# TMS320VC5509AMINI.net
KiCad netlist of a schematic drawn in Altium Designer
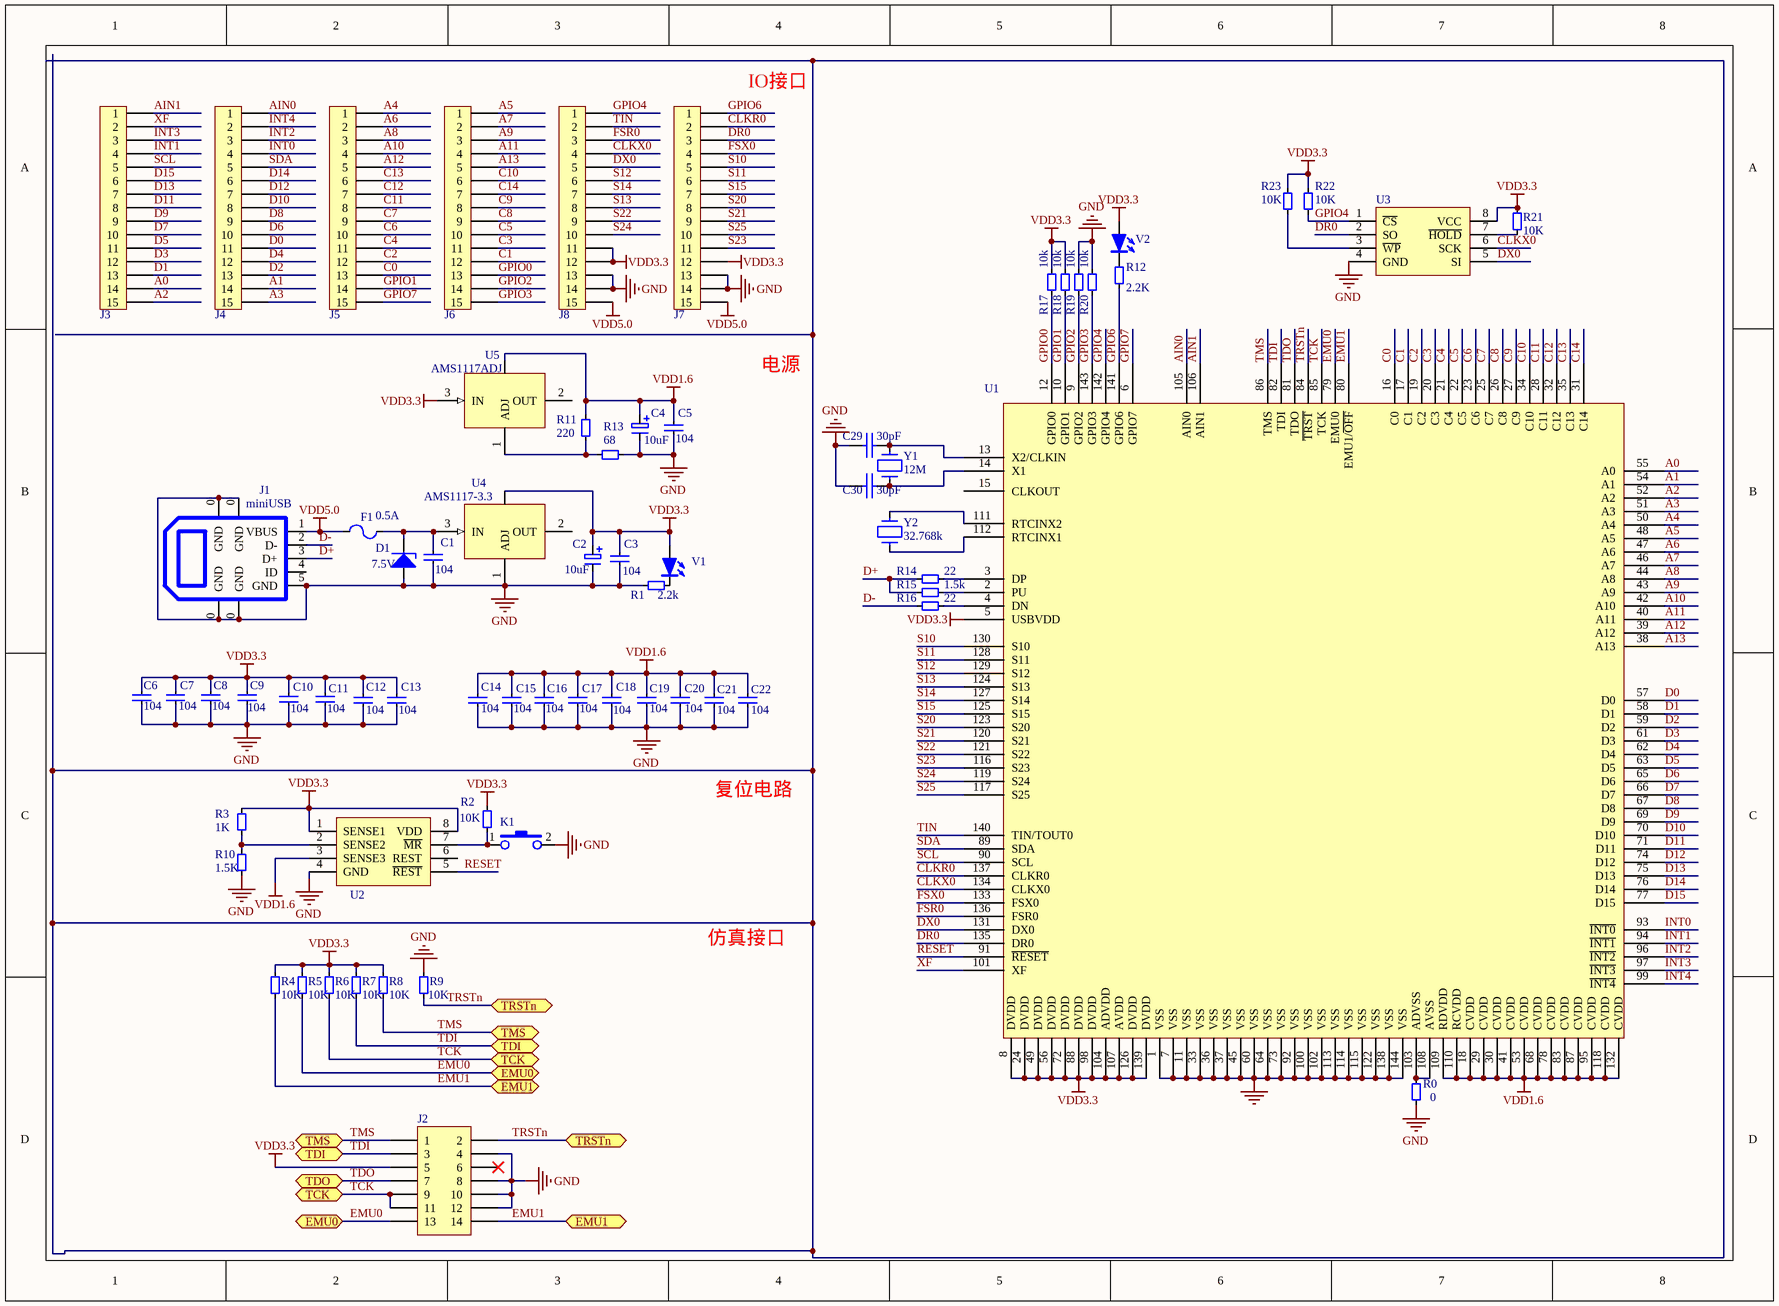
[diagram p0: TMS320VC5509AMINI.SchDoc]

(export (version "E")
  (design (tool "Eeschema 10.0.6"))
  (components
    (comp (ref "C1") (value "104") (footprint "0805_C_M") (libsource (lib "电容系列") (part "C3")))
    (comp (ref "C2") (value "10uF") (footprint "CAP-B") (libsource (lib "电容系列") (part "E3")))
    (comp (ref "C3") (value "104") (footprint "0805_C_M") (libsource (lib "电容系列") (part "C3")))
    (comp (ref "C4") (value "10uF") (footprint "CAP-B") (libsource (lib "电容系列") (part "E3")))
    (comp (ref "C5") (value "104") (footprint "0805_C_M") (libsource (lib "电容系列") (part "C3")))
    (comp (ref "C6") (value "104") (footprint "0805_C_M") (libsource (lib "电容系列") (part "C3")))
    (comp (ref "C7") (value "104") (footprint "0805_C_M") (libsource (lib "电容系列") (part "C3")))
    (comp (ref "C8") (value "104") (footprint "0805_C_M") (libsource (lib "电容系列") (part "C3")))
    (comp (ref "C9") (value "104") (footprint "0805_C_M") (libsource (lib "电容系列") (part "C3")))
    (comp (ref "C10") (value "104") (footprint "0805_C_M") (libsource (lib "电容系列") (part "C3")))
    (comp (ref "C11") (value "104") (footprint "0805_C_M") (libsource (lib "电容系列") (part "C3")))
    (comp (ref "C12") (value "104") (footprint "0805_C_M") (libsource (lib "电容系列") (part "C3")))
    (comp (ref "C13") (value "104") (footprint "0805_C_M") (libsource (lib "电容系列") (part "C3")))
    (comp (ref "C14") (value "104") (footprint "0805_C_M") (libsource (lib "电容系列") (part "C3")))
    (comp (ref "C15") (value "104") (footprint "0805_C_M") (libsource (lib "电容系列") (part "C3")))
    (comp (ref "C16") (value "104") (footprint "0805_C_M") (libsource (lib "电容系列") (part "C3")))
    (comp (ref "C17") (value "104") (footprint "0805_C_M") (libsource (lib "电容系列") (part "C3")))
    (comp (ref "C18") (value "104") (footprint "0805_C_M") (libsource (lib "电容系列") (part "C3")))
    (comp (ref "C19") (value "104") (footprint "0805_C_M") (libsource (lib "电容系列") (part "C3")))
    (comp (ref "C20") (value "104") (footprint "0805_C_M") (libsource (lib "电容系列") (part "C3")))
    (comp (ref "C21") (value "104") (footprint "0805_C_M") (libsource (lib "电容系列") (part "C3")))
    (comp (ref "C22") (value "104") (footprint "0805_C_M") (libsource (lib "电容系列") (part "C3")))
    (comp (ref "C29") (value "30pF") (footprint "0805_C_M") (libsource (lib "电容系列") (part "C1")))
    (comp (ref "C30") (value "30pF") (footprint "0805_C_M") (libsource (lib "电容系列") (part "C1")))
    (comp (ref "D1") (value "7.5V") (footprint "1206D") (libsource (lib "二极管") (part "D4")))
    (comp (ref "F1") (value "0.5A") (footprint "1812F") (libsource (lib "常用库") (part "FUSE1")))
    (comp (ref "J1") (value "miniUSB") (footprint "MINIUSB-S") (libsource (lib "Connector") (part "miniUSB")))
    (comp (ref "J2")
      (value "Header 7X2")
      (footprint "JTAG14")
      (description "Header, 7-Pin, Dual row")
      (fields (field (name "PUBLISHER") "Altium Limited"))
      (libsource (lib "myproject") (part "Header 7X2"))
    )
    (comp (ref "J3") (value "SIP15") (footprint "SIP15_2.54") (libsource (lib "DIP_SIP") (part "SIP15")))
    (comp (ref "J4") (value "SIP15") (footprint "SIP15_2.54") (libsource (lib "DIP_SIP") (part "SIP15")))
    (comp (ref "J5") (value "SIP15") (footprint "SIP15_2.54") (libsource (lib "DIP_SIP") (part "SIP15")))
    (comp (ref "J6") (value "SIP15") (footprint "SIP15_2.54") (libsource (lib "DIP_SIP") (part "SIP15")))
    (comp (ref "J7") (value "SIP15") (footprint "SIP15_2.54") (libsource (lib "DIP_SIP") (part "SIP15")))
    (comp (ref "J8") (value "SIP15") (footprint "SIP15_2.54") (libsource (lib "DIP_SIP") (part "SIP15")))
    (comp (ref "K1") (value "KEY1") (footprint "KEY2") (libsource (lib "Common") (part "KEY1")))
    (comp (ref "R0") (value "0") (footprint "0805_R_M") (libsource (lib "电阻系列") (part "R3")))
    (comp (ref "R1") (value "2.2k") (footprint "0805_R_M") (libsource (lib "电阻系列") (part "R3")))
    (comp (ref "R2") (value "10K") (footprint "0805_R_M") (libsource (lib "电阻系列") (part "R3")))
    (comp (ref "R3") (value "1K") (footprint "0805_R_M") (libsource (lib "电阻系列") (part "R3")))
    (comp (ref "R4") (value "10K") (footprint "0805_R_M") (libsource (lib "电阻系列") (part "R3")))
    (comp (ref "R5") (value "10K") (footprint "0805_R_M") (libsource (lib "电阻系列") (part "R3")))
    (comp (ref "R6") (value "10K") (footprint "0805_R_M") (libsource (lib "电阻系列") (part "R3")))
    (comp (ref "R7") (value "10K") (footprint "0805_R_M") (libsource (lib "电阻系列") (part "R3")))
    (comp (ref "R8") (value "10K") (footprint "0805_R_M") (libsource (lib "电阻系列") (part "R3")))
    (comp (ref "R9") (value "10K") (footprint "0805_R_M") (libsource (lib "电阻系列") (part "R3")))
    (comp (ref "R10") (value "1.5K") (footprint "0805_R_M") (libsource (lib "电阻系列") (part "R3")))
    (comp (ref "R11") (value "220") (footprint "0805_R_M") (libsource (lib "电阻系列") (part "R3")))
    (comp (ref "R12") (value "2.2K") (footprint "0805_R_M") (libsource (lib "电阻系列") (part "R3")))
    (comp (ref "R13") (value "68") (footprint "0805_R_M") (libsource (lib "电阻系列") (part "R3")))
    (comp (ref "R14") (value "22") (footprint "0805_R_M") (libsource (lib "电阻系列") (part "R3")))
    (comp (ref "R15") (value "1.5k") (footprint "0805_R_M") (libsource (lib "电阻系列") (part "R3")))
    (comp (ref "R16") (value "22") (footprint "0805_R_M") (libsource (lib "电阻系列") (part "R3")))
    (comp (ref "R17") (value "10k") (footprint "0805_R_M") (libsource (lib "电阻系列") (part "R3")))
    (comp (ref "R18") (value "10k") (footprint "0805_R_M") (libsource (lib "电阻系列") (part "R3")))
    (comp (ref "R19") (value "10k") (footprint "0805_R_M") (libsource (lib "电阻系列") (part "R3")))
    (comp (ref "R20") (value "10k") (footprint "0805_R_M") (libsource (lib "电阻系列") (part "R3")))
    (comp (ref "R21") (value "10K") (footprint "0805_R_M") (libsource (lib "电阻系列") (part "R3")))
    (comp (ref "R22") (value "10K") (footprint "0805_R_M") (libsource (lib "电阻系列") (part "R3")))
    (comp (ref "R23") (value "10K") (footprint "0805_R_M") (libsource (lib "电阻系列") (part "R3")))
    (comp (ref "U1")
      (value "TMS320VC5509A")
      (footprint "TMS320C5509APGE")
      (description "TMS320VC5509")
      (libsource (lib "*") (part "TMS320VC5509A"))
    )
    (comp (ref "U2")
      (value "TPS3307-18")
      (footprint "SOP8")
      (libsource (lib "myproject") (part "TPS3307-18"))
    )
    (comp (ref "U3") (value "AT25256") (footprint "SOP8") (libsource (lib "Common") (part "AT25XXX")))
    (comp (ref "U4") (value "AMS1117-3.3") (footprint "LM1117") (libsource (lib "电源（专用）") (part "1117")))
    (comp (ref "U5") (value "AMS1117ADJ") (footprint "LM1117") (libsource (lib "电源（专用）") (part "1117")))
    (comp (ref "V1") (value "LED") (footprint "0805D") (libsource (lib "发光管、数码管") (part "LED2")))
    (comp (ref "V2") (value "LED") (footprint "0805D") (libsource (lib "发光管、数码管") (part "LED2")))
    (comp (ref "Y1") (value "12M") (footprint "Component:5032") (libsource (lib "常用库") (part "CY1")))
    (comp (ref "Y2") (value "32.768k") (footprint "DT-26") (libsource (lib "常用库") (part "CY1")))
  )
  (nets
    (net (code "1") (name "/A0") (class "Default")
      (node (ref "J3") (pin "14") (pinfunction "14_14") (pintype "passive"))
      (node (ref "U1") (pin "55") (pinfunction "A0_55") (pintype "passive"))
    )
    (net (code "2") (name "/A1") (class "Default")
      (node (ref "J4") (pin "14") (pinfunction "14_14") (pintype "passive"))
      (node (ref "U1") (pin "54") (pinfunction "A1_54") (pintype "passive"))
    )
    (net (code "3") (name "/A2") (class "Default")
      (node (ref "J3") (pin "15") (pinfunction "15_15") (pintype "passive"))
      (node (ref "U1") (pin "52") (pinfunction "A2_52") (pintype "passive"))
    )
    (net (code "4") (name "/A3") (class "Default")
      (node (ref "J4") (pin "15") (pinfunction "15_15") (pintype "passive"))
      (node (ref "U1") (pin "51") (pinfunction "A3_51") (pintype "passive"))
    )
    (net (code "5") (name "/A4") (class "Default")
      (node (ref "J5") (pin "1") (pinfunction "1_1") (pintype "passive"))
      (node (ref "U1") (pin "50") (pinfunction "A4_50") (pintype "passive"))
    )
    (net (code "6") (name "/A5") (class "Default")
      (node (ref "J6") (pin "1") (pinfunction "1_1") (pintype "passive"))
      (node (ref "U1") (pin "48") (pinfunction "A5_48") (pintype "passive"))
    )
    (net (code "7") (name "/A6") (class "Default")
      (node (ref "J5") (pin "2") (pinfunction "2_2") (pintype "passive"))
      (node (ref "U1") (pin "47") (pinfunction "A6_47") (pintype "passive"))
    )
    (net (code "8") (name "/A7") (class "Default")
      (node (ref "J6") (pin "2") (pinfunction "2_2") (pintype "passive"))
      (node (ref "U1") (pin "46") (pinfunction "A7_46") (pintype "passive"))
    )
    (net (code "9") (name "/A8") (class "Default")
      (node (ref "J5") (pin "3") (pinfunction "3_3") (pintype "passive"))
      (node (ref "U1") (pin "44") (pinfunction "A8_44") (pintype "passive"))
    )
    (net (code "10") (name "/A9") (class "Default")
      (node (ref "J6") (pin "3") (pinfunction "3_3") (pintype "passive"))
      (node (ref "U1") (pin "43") (pinfunction "A9_43") (pintype "passive"))
    )
    (net (code "11") (name "/A10") (class "Default")
      (node (ref "J5") (pin "4") (pinfunction "4_4") (pintype "passive"))
      (node (ref "U1") (pin "42") (pinfunction "A10_42") (pintype "passive"))
    )
    (net (code "12") (name "/A11") (class "Default")
      (node (ref "J6") (pin "4") (pinfunction "4_4") (pintype "passive"))
      (node (ref "U1") (pin "40") (pinfunction "A11_40") (pintype "passive"))
    )
    (net (code "13") (name "/A12") (class "Default")
      (node (ref "J5") (pin "5") (pinfunction "5_5") (pintype "passive"))
      (node (ref "U1") (pin "39") (pinfunction "A12_39") (pintype "passive"))
    )
    (net (code "14") (name "/A13") (class "Default")
      (node (ref "J6") (pin "5") (pinfunction "5_5") (pintype "passive"))
      (node (ref "U1") (pin "38") (pinfunction "A13_38") (pintype "passive"))
    )
    (net (code "15") (name "/AIN0") (class "Default")
      (node (ref "J4") (pin "1") (pinfunction "1_1") (pintype "passive"))
      (node (ref "U1") (pin "105") (pinfunction "AIN0_105") (pintype "passive"))
    )
    (net (code "16") (name "/AIN1") (class "Default")
      (node (ref "J3") (pin "1") (pinfunction "1_1") (pintype "passive"))
      (node (ref "U1") (pin "106") (pinfunction "AIN1_106") (pintype "passive"))
    )
    (net (code "17") (name "/C0") (class "Default")
      (node (ref "J5") (pin "13") (pinfunction "13_13") (pintype "passive"))
      (node (ref "U1") (pin "16") (pinfunction "C0_16") (pintype "passive"))
    )
    (net (code "18") (name "/C1") (class "Default")
      (node (ref "J6") (pin "12") (pinfunction "12_12") (pintype "passive"))
      (node (ref "U1") (pin "17") (pinfunction "C1_17") (pintype "passive"))
    )
    (net (code "19") (name "/C2") (class "Default")
      (node (ref "J5") (pin "12") (pinfunction "12_12") (pintype "passive"))
      (node (ref "U1") (pin "19") (pinfunction "C2_19") (pintype "passive"))
    )
    (net (code "20") (name "/C3") (class "Default")
      (node (ref "J6") (pin "11") (pinfunction "11_11") (pintype "passive"))
      (node (ref "U1") (pin "20") (pinfunction "C3_20") (pintype "passive"))
    )
    (net (code "21") (name "/C4") (class "Default")
      (node (ref "J5") (pin "11") (pinfunction "11_11") (pintype "passive"))
      (node (ref "U1") (pin "21") (pinfunction "C4_21") (pintype "passive"))
    )
    (net (code "22") (name "/C5") (class "Default")
      (node (ref "J6") (pin "10") (pinfunction "10_10") (pintype "passive"))
      (node (ref "U1") (pin "22") (pinfunction "C5_22") (pintype "passive"))
    )
    (net (code "23") (name "/C6") (class "Default")
      (node (ref "J5") (pin "10") (pinfunction "10_10") (pintype "passive"))
      (node (ref "U1") (pin "23") (pinfunction "C6_23") (pintype "passive"))
    )
    (net (code "24") (name "/C7") (class "Default")
      (node (ref "J5") (pin "9") (pinfunction "9_9") (pintype "passive"))
      (node (ref "U1") (pin "25") (pinfunction "C7_25") (pintype "passive"))
    )
    (net (code "25") (name "/C8") (class "Default")
      (node (ref "J6") (pin "9") (pinfunction "9_9") (pintype "passive"))
      (node (ref "U1") (pin "26") (pinfunction "C8_26") (pintype "passive"))
    )
    (net (code "26") (name "/C9") (class "Default")
      (node (ref "J6") (pin "8") (pinfunction "8_8") (pintype "passive"))
      (node (ref "U1") (pin "27") (pinfunction "C9_27") (pintype "passive"))
    )
    (net (code "27") (name "/C10") (class "Default")
      (node (ref "J6") (pin "6") (pinfunction "6_6") (pintype "passive"))
      (node (ref "U1") (pin "34") (pinfunction "C10_34") (pintype "passive"))
    )
    (net (code "28") (name "/C11") (class "Default")
      (node (ref "J5") (pin "8") (pinfunction "8_8") (pintype "passive"))
      (node (ref "U1") (pin "28") (pinfunction "C11_28") (pintype "passive"))
    )
    (net (code "29") (name "/C12") (class "Default")
      (node (ref "J5") (pin "7") (pinfunction "7_7") (pintype "passive"))
      (node (ref "U1") (pin "32") (pinfunction "C12_32") (pintype "passive"))
    )
    (net (code "30") (name "/C13") (class "Default")
      (node (ref "J5") (pin "6") (pinfunction "6_6") (pintype "passive"))
      (node (ref "U1") (pin "35") (pinfunction "C13_35") (pintype "passive"))
    )
    (net (code "31") (name "/C14") (class "Default")
      (node (ref "J6") (pin "7") (pinfunction "7_7") (pintype "passive"))
      (node (ref "U1") (pin "31") (pinfunction "C14_31") (pintype "passive"))
    )
    (net (code "32") (name "/CLKR0") (class "Default")
      (node (ref "J7") (pin "2") (pinfunction "2_2") (pintype "passive"))
      (node (ref "U1") (pin "137") (pinfunction "CLKR0_137") (pintype "passive"))
    )
    (net (code "33") (name "/CLKX0") (class "Default")
      (node (ref "J8") (pin "4") (pinfunction "4_4") (pintype "passive"))
      (node (ref "U1") (pin "134") (pinfunction "CLKX0_134") (pintype "passive"))
      (node (ref "U3") (pin "6") (pinfunction "SCK_6") (pintype "passive"))
    )
    (net (code "34") (name "/D+") (class "Default")
      (node (ref "J1") (pin "3") (pinfunction "D+_3") (pintype "passive"))
      (node (ref "R14") (pin "2") (pinfunction "2_2") (pintype "passive"))
      (node (ref "R15") (pin "2") (pinfunction "2_2") (pintype "passive"))
    )
    (net (code "35") (name "/D-") (class "Default")
      (node (ref "J1") (pin "2") (pinfunction "D-_2") (pintype "passive"))
      (node (ref "R16") (pin "2") (pinfunction "2_2") (pintype "passive"))
    )
    (net (code "36") (name "/D0") (class "Default")
      (node (ref "J4") (pin "11") (pinfunction "11_11") (pintype "passive"))
      (node (ref "U1") (pin "57") (pinfunction "D0_57") (pintype "passive"))
    )
    (net (code "37") (name "/D1") (class "Default")
      (node (ref "J3") (pin "13") (pinfunction "13_13") (pintype "passive"))
      (node (ref "U1") (pin "58") (pinfunction "D1_58") (pintype "passive"))
    )
    (net (code "38") (name "/D2") (class "Default")
      (node (ref "J4") (pin "13") (pinfunction "13_13") (pintype "passive"))
      (node (ref "U1") (pin "59") (pinfunction "D2_59") (pintype "passive"))
    )
    (net (code "39") (name "/D3") (class "Default")
      (node (ref "J3") (pin "12") (pinfunction "12_12") (pintype "passive"))
      (node (ref "U1") (pin "61") (pinfunction "D3_61") (pintype "passive"))
    )
    (net (code "40") (name "/D4") (class "Default")
      (node (ref "J4") (pin "12") (pinfunction "12_12") (pintype "passive"))
      (node (ref "U1") (pin "62") (pinfunction "D4_62") (pintype "passive"))
    )
    (net (code "41") (name "/D5") (class "Default")
      (node (ref "J3") (pin "11") (pinfunction "11_11") (pintype "passive"))
      (node (ref "U1") (pin "63") (pinfunction "D5_63") (pintype "passive"))
    )
    (net (code "42") (name "/D6") (class "Default")
      (node (ref "J4") (pin "10") (pinfunction "10_10") (pintype "passive"))
      (node (ref "U1") (pin "65") (pinfunction "D6_65") (pintype "passive"))
    )
    (net (code "43") (name "/D7") (class "Default")
      (node (ref "J3") (pin "10") (pinfunction "10_10") (pintype "passive"))
      (node (ref "U1") (pin "66") (pinfunction "D7_66") (pintype "passive"))
    )
    (net (code "44") (name "/D8") (class "Default")
      (node (ref "J4") (pin "9") (pinfunction "9_9") (pintype "passive"))
      (node (ref "U1") (pin "67") (pinfunction "D8_67") (pintype "passive"))
    )
    (net (code "45") (name "/D9") (class "Default")
      (node (ref "J3") (pin "9") (pinfunction "9_9") (pintype "passive"))
      (node (ref "U1") (pin "69") (pinfunction "D9_69") (pintype "passive"))
    )
    (net (code "46") (name "/D10") (class "Default")
      (node (ref "J4") (pin "8") (pinfunction "8_8") (pintype "passive"))
      (node (ref "U1") (pin "70") (pinfunction "D10_70") (pintype "passive"))
    )
    (net (code "47") (name "/D11") (class "Default")
      (node (ref "J3") (pin "8") (pinfunction "8_8") (pintype "passive"))
      (node (ref "U1") (pin "71") (pinfunction "D11_71") (pintype "passive"))
    )
    (net (code "48") (name "/D12") (class "Default")
      (node (ref "J4") (pin "7") (pinfunction "7_7") (pintype "passive"))
      (node (ref "U1") (pin "74") (pinfunction "D12_74") (pintype "passive"))
    )
    (net (code "49") (name "/D13") (class "Default")
      (node (ref "J3") (pin "7") (pinfunction "7_7") (pintype "passive"))
      (node (ref "U1") (pin "75") (pinfunction "D13_75") (pintype "passive"))
    )
    (net (code "50") (name "/D14") (class "Default")
      (node (ref "J4") (pin "6") (pinfunction "6_6") (pintype "passive"))
      (node (ref "U1") (pin "76") (pinfunction "D14_76") (pintype "passive"))
    )
    (net (code "51") (name "/D15") (class "Default")
      (node (ref "J3") (pin "6") (pinfunction "6_6") (pintype "passive"))
      (node (ref "U1") (pin "77") (pinfunction "D15_77") (pintype "passive"))
    )
    (net (code "52") (name "/DR0") (class "Default")
      (node (ref "J7") (pin "3") (pinfunction "3_3") (pintype "passive"))
      (node (ref "U1") (pin "135") (pinfunction "DR0_135") (pintype "passive"))
      (node (ref "U3") (pin "2") (pinfunction "SO_2") (pintype "passive"))
    )
    (net (code "53") (name "/DX0") (class "Default")
      (node (ref "J8") (pin "5") (pinfunction "5_5") (pintype "passive"))
      (node (ref "U1") (pin "131") (pinfunction "DX0_131") (pintype "passive"))
      (node (ref "U3") (pin "5") (pinfunction "SI_5") (pintype "passive"))
    )
    (net (code "54") (name "/EMU0") (class "Default")
      (node (ref "J2") (pin "13") (pinfunction "13_13") (pintype "passive"))
      (node (ref "R5") (pin "1") (pinfunction "1_1") (pintype "passive"))
      (node (ref "U1") (pin "79") (pinfunction "EMU0_79") (pintype "passive"))
    )
    (net (code "55") (name "/EMU1") (class "Default")
      (node (ref "J2") (pin "14") (pinfunction "14_14") (pintype "passive"))
      (node (ref "R4") (pin "1") (pinfunction "1_1") (pintype "passive"))
      (node (ref "U1") (pin "80") (pinfunction "EMU1/~{OFF}_80") (pintype "passive"))
    )
    (net (code "56") (name "/FSR0") (class "Default")
      (node (ref "J8") (pin "3") (pinfunction "3_3") (pintype "passive"))
      (node (ref "U1") (pin "136") (pinfunction "FSR0_136") (pintype "passive"))
    )
    (net (code "57") (name "/FSX0") (class "Default")
      (node (ref "J7") (pin "4") (pinfunction "4_4") (pintype "passive"))
      (node (ref "U1") (pin "133") (pinfunction "FSX0_133") (pintype "passive"))
    )
    (net (code "58") (name "/GPIO0") (class "Default")
      (node (ref "J6") (pin "13") (pinfunction "13_13") (pintype "passive"))
      (node (ref "R17") (pin "2") (pinfunction "2_2") (pintype "passive"))
      (node (ref "U1") (pin "12") (pinfunction "GPIO0_12") (pintype "passive"))
    )
    (net (code "59") (name "/GPIO1") (class "Default")
      (node (ref "J5") (pin "14") (pinfunction "14_14") (pintype "passive"))
      (node (ref "R18") (pin "2") (pinfunction "2_2") (pintype "passive"))
      (node (ref "U1") (pin "10") (pinfunction "GPIO1_10") (pintype "passive"))
    )
    (net (code "60") (name "/GPIO2") (class "Default")
      (node (ref "J6") (pin "14") (pinfunction "14_14") (pintype "passive"))
      (node (ref "R19") (pin "2") (pinfunction "2_2") (pintype "passive"))
      (node (ref "U1") (pin "9") (pinfunction "GPIO2_9") (pintype "passive"))
    )
    (net (code "61") (name "/GPIO3") (class "Default")
      (node (ref "J6") (pin "15") (pinfunction "15_15") (pintype "passive"))
      (node (ref "R20") (pin "2") (pinfunction "2_2") (pintype "passive"))
      (node (ref "U1") (pin "143") (pinfunction "GPIO3_143") (pintype "passive"))
    )
    (net (code "62") (name "/GPIO4") (class "Default")
      (node (ref "J8") (pin "1") (pinfunction "1_1") (pintype "passive"))
      (node (ref "R22") (pin "1") (pinfunction "1_1") (pintype "passive"))
      (node (ref "U1") (pin "142") (pinfunction "GPIO4_142") (pintype "passive"))
      (node (ref "U3") (pin "1") (pinfunction "~{CS}_1") (pintype "passive"))
    )
    (net (code "63") (name "/GPIO6") (class "Default")
      (node (ref "J7") (pin "1") (pinfunction "1_1") (pintype "passive"))
      (node (ref "R12") (pin "2") (pinfunction "2_2") (pintype "passive"))
      (node (ref "U1") (pin "141") (pinfunction "GPIO6_141") (pintype "passive"))
    )
    (net (code "64") (name "/GPIO7") (class "Default")
      (node (ref "J5") (pin "15") (pinfunction "15_15") (pintype "passive"))
      (node (ref "U1") (pin "6") (pinfunction "GPIO7_6") (pintype "passive"))
    )
    (net (code "65") (name "/INT0") (class "Default")
      (node (ref "J4") (pin "4") (pinfunction "4_4") (pintype "passive"))
      (node (ref "U1") (pin "93") (pinfunction "~{INT0}_93") (pintype "passive"))
    )
    (net (code "66") (name "/INT1") (class "Default")
      (node (ref "J3") (pin "4") (pinfunction "4_4") (pintype "passive"))
      (node (ref "U1") (pin "94") (pinfunction "~{INT1}_94") (pintype "passive"))
    )
    (net (code "67") (name "/INT2") (class "Default")
      (node (ref "J4") (pin "3") (pinfunction "3_3") (pintype "passive"))
      (node (ref "U1") (pin "96") (pinfunction "~{INT2}_96") (pintype "passive"))
    )
    (net (code "68") (name "/INT3") (class "Default")
      (node (ref "J3") (pin "3") (pinfunction "3_3") (pintype "passive"))
      (node (ref "U1") (pin "97") (pinfunction "~{INT3}_97") (pintype "passive"))
    )
    (net (code "69") (name "/INT4") (class "Default")
      (node (ref "J4") (pin "2") (pinfunction "2_2") (pintype "passive"))
      (node (ref "U1") (pin "99") (pinfunction "~{INT4}_99") (pintype "passive"))
    )
    (net (code "70") (name "/RESET") (class "Default")
      (node (ref "U1") (pin "91") (pinfunction "~{RESET}_91") (pintype "passive"))
      (node (ref "U2") (pin "5") (pinfunction "~{REST}_5") (pintype "passive"))
    )
    (net (code "71") (name "/S10") (class "Default")
      (node (ref "J7") (pin "5") (pinfunction "5_5") (pintype "passive"))
      (node (ref "U1") (pin "130") (pinfunction "S10_130") (pintype "passive"))
    )
    (net (code "72") (name "/S11") (class "Default")
      (node (ref "J7") (pin "6") (pinfunction "6_6") (pintype "passive"))
      (node (ref "U1") (pin "128") (pinfunction "S11_128") (pintype "passive"))
    )
    (net (code "73") (name "/S12") (class "Default")
      (node (ref "J8") (pin "6") (pinfunction "6_6") (pintype "passive"))
      (node (ref "U1") (pin "129") (pinfunction "S12_129") (pintype "passive"))
    )
    (net (code "74") (name "/S13") (class "Default")
      (node (ref "J8") (pin "8") (pinfunction "8_8") (pintype "passive"))
      (node (ref "U1") (pin "124") (pinfunction "S13_124") (pintype "passive"))
    )
    (net (code "75") (name "/S14") (class "Default")
      (node (ref "J8") (pin "7") (pinfunction "7_7") (pintype "passive"))
      (node (ref "U1") (pin "127") (pinfunction "S14_127") (pintype "passive"))
    )
    (net (code "76") (name "/S15") (class "Default")
      (node (ref "J7") (pin "7") (pinfunction "7_7") (pintype "passive"))
      (node (ref "U1") (pin "125") (pinfunction "S15_125") (pintype "passive"))
    )
    (net (code "77") (name "/S20") (class "Default")
      (node (ref "J7") (pin "8") (pinfunction "8_8") (pintype "passive"))
      (node (ref "U1") (pin "123") (pinfunction "S20_123") (pintype "passive"))
    )
    (net (code "78") (name "/S21") (class "Default")
      (node (ref "J7") (pin "9") (pinfunction "9_9") (pintype "passive"))
      (node (ref "U1") (pin "120") (pinfunction "S21_120") (pintype "passive"))
    )
    (net (code "79") (name "/S22") (class "Default")
      (node (ref "J8") (pin "9") (pinfunction "9_9") (pintype "passive"))
      (node (ref "U1") (pin "121") (pinfunction "S22_121") (pintype "passive"))
    )
    (net (code "80") (name "/S23") (class "Default")
      (node (ref "J7") (pin "11") (pinfunction "11_11") (pintype "passive"))
      (node (ref "U1") (pin "116") (pinfunction "S23_116") (pintype "passive"))
    )
    (net (code "81") (name "/S24") (class "Default")
      (node (ref "J8") (pin "10") (pinfunction "10_10") (pintype "passive"))
      (node (ref "U1") (pin "119") (pinfunction "S24_119") (pintype "passive"))
    )
    (net (code "82") (name "/S25") (class "Default")
      (node (ref "J7") (pin "10") (pinfunction "10_10") (pintype "passive"))
      (node (ref "U1") (pin "117") (pinfunction "S25_117") (pintype "passive"))
    )
    (net (code "83") (name "/SCL") (class "Default")
      (node (ref "J3") (pin "5") (pinfunction "5_5") (pintype "passive"))
      (node (ref "U1") (pin "90") (pinfunction "SCL_90") (pintype "passive"))
    )
    (net (code "84") (name "/SDA") (class "Default")
      (node (ref "J4") (pin "5") (pinfunction "5_5") (pintype "passive"))
      (node (ref "U1") (pin "89") (pinfunction "SDA_89") (pintype "passive"))
    )
    (net (code "85") (name "/TCK") (class "Default")
      (node (ref "J2") (pin "11") (pinfunction "11_11") (pintype "passive"))
      (node (ref "J2") (pin "9") (pinfunction "9_9") (pintype "passive"))
      (node (ref "R6") (pin "1") (pinfunction "1_1") (pintype "passive"))
      (node (ref "U1") (pin "85") (pinfunction "TCK_85") (pintype "passive"))
    )
    (net (code "86") (name "/TDI") (class "Default")
      (node (ref "J2") (pin "3") (pinfunction "3_3") (pintype "passive"))
      (node (ref "R7") (pin "1") (pinfunction "1_1") (pintype "passive"))
      (node (ref "U1") (pin "82") (pinfunction "TDI_82") (pintype "passive"))
    )
    (net (code "87") (name "/TDO") (class "Default")
      (node (ref "J2") (pin "7") (pinfunction "7_7") (pintype "passive"))
      (node (ref "U1") (pin "81") (pinfunction "TDO_81") (pintype "passive"))
    )
    (net (code "88") (name "/TIN") (class "Default")
      (node (ref "J8") (pin "2") (pinfunction "2_2") (pintype "passive"))
      (node (ref "U1") (pin "140") (pinfunction "TIN/TOUT0_140") (pintype "passive"))
    )
    (net (code "89") (name "/TMS") (class "Default")
      (node (ref "J2") (pin "1") (pinfunction "1_1") (pintype "passive"))
      (node (ref "R8") (pin "1") (pinfunction "1_1") (pintype "passive"))
      (node (ref "U1") (pin "86") (pinfunction "TMS_86") (pintype "passive"))
    )
    (net (code "90") (name "/TRSTn") (class "Default")
      (node (ref "J2") (pin "2") (pinfunction "2_2") (pintype "passive"))
      (node (ref "R9") (pin "1") (pinfunction "1_1") (pintype "passive"))
      (node (ref "U1") (pin "84") (pinfunction "~{TRST}_84") (pintype "passive"))
    )
    (net (code "91") (name "/XF") (class "Default")
      (node (ref "J3") (pin "2") (pinfunction "2_2") (pintype "passive"))
      (node (ref "U1") (pin "101") (pinfunction "XF_101") (pintype "passive"))
    )
    (net (code "92") (name "GND") (class "Default")
      (node (ref "C1") (pin "2") (pinfunction "2_2") (pintype "passive"))
      (node (ref "C10") (pin "2") (pinfunction "2_2") (pintype "passive"))
      (node (ref "C11") (pin "2") (pinfunction "2_2") (pintype "passive"))
      (node (ref "C12") (pin "2") (pinfunction "2_2") (pintype "passive"))
      (node (ref "C13") (pin "2") (pinfunction "2_2") (pintype "passive"))
      (node (ref "C14") (pin "2") (pinfunction "2_2") (pintype "passive"))
      (node (ref "C15") (pin "2") (pinfunction "2_2") (pintype "passive"))
      (node (ref "C16") (pin "2") (pinfunction "2_2") (pintype "passive"))
      (node (ref "C17") (pin "2") (pinfunction "2_2") (pintype "passive"))
      (node (ref "C18") (pin "2") (pinfunction "2_2") (pintype "passive"))
      (node (ref "C19") (pin "2") (pinfunction "2_2") (pintype "passive"))
      (node (ref "C2") (pin "2") (pinfunction "2_2") (pintype "passive"))
      (node (ref "C20") (pin "2") (pinfunction "2_2") (pintype "passive"))
      (node (ref "C21") (pin "1") (pinfunction "1_1") (pintype "passive"))
      (node (ref "C22") (pin "1") (pinfunction "1_1") (pintype "passive"))
      (node (ref "C29") (pin "1") (pinfunction "1_1") (pintype "passive"))
      (node (ref "C3") (pin "2") (pinfunction "2_2") (pintype "passive"))
      (node (ref "C30") (pin "1") (pinfunction "1_1") (pintype "passive"))
      (node (ref "C4") (pin "2") (pinfunction "2_2") (pintype "passive"))
      (node (ref "C5") (pin "2") (pinfunction "2_2") (pintype "passive"))
      (node (ref "C6") (pin "2") (pinfunction "2_2") (pintype "passive"))
      (node (ref "C7") (pin "2") (pinfunction "2_2") (pintype "passive"))
      (node (ref "C8") (pin "2") (pinfunction "2_2") (pintype "passive"))
      (node (ref "C9") (pin "2") (pinfunction "2_2") (pintype "passive"))
      (node (ref "D1") (pin "1") (pinfunction "1_1") (pintype "passive"))
      (node (ref "J1") (pin "0") (pinfunction "GND_0") (pintype "passive"))
      (node (ref "J1") (pin "5") (pinfunction "GND_5") (pintype "passive"))
      (node (ref "J2") (pin "10") (pinfunction "10_10") (pintype "passive"))
      (node (ref "J2") (pin "12") (pinfunction "12_12") (pintype "passive"))
      (node (ref "J2") (pin "4") (pinfunction "4_4") (pintype "passive"))
      (node (ref "J2") (pin "8") (pinfunction "8_8") (pintype "passive"))
      (node (ref "J7") (pin "13") (pinfunction "13_13") (pintype "passive"))
      (node (ref "J7") (pin "14") (pinfunction "14_14") (pintype "passive"))
      (node (ref "J8") (pin "13") (pinfunction "13_13") (pintype "passive"))
      (node (ref "J8") (pin "14") (pinfunction "14_14") (pintype "passive"))
      (node (ref "K1") (pin "2") (pintype "passive"))
      (node (ref "R0") (pin "1") (pinfunction "1_1") (pintype "passive"))
      (node (ref "R1") (pin "2") (pinfunction "2_2") (pintype "passive"))
      (node (ref "R10") (pin "2") (pinfunction "2_2") (pintype "passive"))
      (node (ref "R13") (pin "2") (pinfunction "2_2") (pintype "passive"))
      (node (ref "R19") (pin "1") (pinfunction "1_1") (pintype "passive"))
      (node (ref "R20") (pin "1") (pinfunction "1_1") (pintype "passive"))
      (node (ref "R9") (pin "2") (pinfunction "2_2") (pintype "passive"))
      (node (ref "U1") (pin "1") (pinfunction "VSS_1") (pintype "passive"))
      (node (ref "U1") (pin "100") (pinfunction "VSS_100") (pintype "passive"))
      (node (ref "U1") (pin "102") (pinfunction "VSS_102") (pintype "passive"))
      (node (ref "U1") (pin "11") (pinfunction "VSS_11") (pintype "passive"))
      (node (ref "U1") (pin "113") (pinfunction "VSS_113") (pintype "passive"))
      (node (ref "U1") (pin "114") (pinfunction "VSS_114") (pintype "passive"))
      (node (ref "U1") (pin "115") (pinfunction "VSS_115") (pintype "passive"))
      (node (ref "U1") (pin "122") (pinfunction "VSS_122") (pintype "passive"))
      (node (ref "U1") (pin "138") (pinfunction "VSS_138") (pintype "passive"))
      (node (ref "U1") (pin "144") (pinfunction "VSS_144") (pintype "passive"))
      (node (ref "U1") (pin "33") (pinfunction "VSS_33") (pintype "passive"))
      (node (ref "U1") (pin "36") (pinfunction "VSS_36") (pintype "passive"))
      (node (ref "U1") (pin "37") (pinfunction "VSS_37") (pintype "passive"))
      (node (ref "U1") (pin "45") (pinfunction "VSS_45") (pintype "passive"))
      (node (ref "U1") (pin "60") (pinfunction "VSS_60") (pintype "passive"))
      (node (ref "U1") (pin "64") (pinfunction "VSS_64") (pintype "passive"))
      (node (ref "U1") (pin "7") (pinfunction "VSS_7") (pintype "passive"))
      (node (ref "U1") (pin "73") (pinfunction "VSS_73") (pintype "passive"))
      (node (ref "U1") (pin "92") (pinfunction "VSS_92") (pintype "passive"))
      (node (ref "U2") (pin "4") (pinfunction "GND_4") (pintype "passive"))
      (node (ref "U3") (pin "4") (pinfunction "GND_4") (pintype "passive"))
      (node (ref "U4") (pin "1") (pinfunction "ADJ_1") (pintype "power_in"))
    )
    (net (code "93") (name "Net-(R1-Pad1)") (class "Default")
      (node (ref "R1") (pin "1") (pinfunction "1_1") (pintype "passive"))
      (node (ref "V1") (pin "2") (pinfunction "2_2") (pintype "passive"))
    )
    (net (code "94") (name "Net-(R12-Pad1)") (class "Default")
      (node (ref "R12") (pin "1") (pinfunction "1_1") (pintype "passive"))
      (node (ref "V2") (pin "2") (pinfunction "2_2") (pintype "passive"))
    )
    (net (code "95") (name "Net-(U1-ADVSS)") (class "Default")
      (node (ref "R0") (pin "2") (pinfunction "2_2") (pintype "passive"))
      (node (ref "U1") (pin "103") (pinfunction "ADVSS_103") (pintype "passive"))
      (node (ref "U1") (pin "108") (pinfunction "AVSS_108") (pintype "passive"))
    )
    (net (code "96") (name "Net-(U1-DN)") (class "Default")
      (node (ref "R16") (pin "1") (pinfunction "1_1") (pintype "passive"))
      (node (ref "U1") (pin "4") (pinfunction "DN_4") (pintype "passive"))
    )
    (net (code "97") (name "Net-(U1-DP)") (class "Default")
      (node (ref "R14") (pin "1") (pinfunction "1_1") (pintype "passive"))
      (node (ref "U1") (pin "3") (pinfunction "DP_3") (pintype "passive"))
    )
    (net (code "98") (name "Net-(U1-PU)") (class "Default")
      (node (ref "R15") (pin "1") (pinfunction "1_1") (pintype "passive"))
      (node (ref "U1") (pin "2") (pinfunction "PU_2") (pintype "passive"))
    )
    (net (code "99") (name "Net-(U1-RTCINX1)") (class "Default")
      (node (ref "U1") (pin "112") (pinfunction "RTCINX1_112") (pintype "passive"))
      (node (ref "Y2") (pin "2") (pinfunction "2_2") (pintype "passive"))
    )
    (net (code "100") (name "Net-(U1-RTCINX2)") (class "Default")
      (node (ref "U1") (pin "111") (pinfunction "RTCINX2_111") (pintype "passive"))
      (node (ref "Y2") (pin "1") (pinfunction "1_1") (pintype "passive"))
    )
    (net (code "101") (name "Net-(U1-X1)") (class "Default")
      (node (ref "C30") (pin "2") (pinfunction "2_2") (pintype "passive"))
      (node (ref "U1") (pin "14") (pinfunction "X1_14") (pintype "passive"))
      (node (ref "Y1") (pin "1") (pinfunction "1_1") (pintype "passive"))
    )
    (net (code "102") (name "Net-(U1-X2{slash}CLKIN)") (class "Default")
      (node (ref "C29") (pin "2") (pinfunction "2_2") (pintype "passive"))
      (node (ref "U1") (pin "13") (pinfunction "X2/CLKIN_13") (pintype "passive"))
      (node (ref "Y1") (pin "2") (pinfunction "2_2") (pintype "passive"))
    )
    (net (code "103") (name "Net-(U2-SENSE2)") (class "Default")
      (node (ref "R10") (pin "1") (pinfunction "1_1") (pintype "passive"))
      (node (ref "R3") (pin "1") (pinfunction "1_1") (pintype "passive"))
      (node (ref "U2") (pin "2") (pinfunction "SENSE2_2") (pintype "passive"))
    )
    (net (code "104") (name "Net-(U2-~{MR})") (class "Default")
      (node (ref "K1") (pin "1") (pintype "passive"))
      (node (ref "R2") (pin "2") (pinfunction "2_2") (pintype "passive"))
      (node (ref "U2") (pin "7") (pinfunction "~{MR}_7") (pintype "passive"))
    )
    (net (code "105") (name "Net-(U3-~{HOLD})") (class "Default")
      (node (ref "R21") (pin "2") (pinfunction "2_2") (pintype "passive"))
      (node (ref "U3") (pin "7") (pinfunction "~{HOLD}_7") (pintype "passive"))
    )
    (net (code "106") (name "Net-(U3-~{WP})") (class "Default")
      (node (ref "R23") (pin "2") (pinfunction "2_2") (pintype "passive"))
      (node (ref "U3") (pin "3") (pinfunction "~{WP}_3") (pintype "passive"))
    )
    (net (code "107") (name "Net-(U4-IN)") (class "Default")
      (node (ref "C1") (pin "1") (pinfunction "1_1") (pintype "passive"))
      (node (ref "D1") (pin "2") (pinfunction "2_2") (pintype "passive"))
      (node (ref "F1") (pin "2") (pintype "input"))
      (node (ref "U4") (pin "3") (pinfunction "IN_3") (pintype "input"))
    )
    (net (code "108") (name "Net-(U5-ADJ)") (class "Default")
      (node (ref "R11") (pin "2") (pinfunction "2_2") (pintype "passive"))
      (node (ref "R13") (pin "1") (pinfunction "1_1") (pintype "passive"))
      (node (ref "U5") (pin "1") (pinfunction "ADJ_1") (pintype "power_in"))
    )
    (net (code "109") (name "VDD1.6") (class "Default")
      (node (ref "C14") (pin "1") (pinfunction "1_1") (pintype "passive"))
      (node (ref "C15") (pin "1") (pinfunction "1_1") (pintype "passive"))
      (node (ref "C16") (pin "1") (pinfunction "1_1") (pintype "passive"))
      (node (ref "C17") (pin "1") (pinfunction "1_1") (pintype "passive"))
      (node (ref "C18") (pin "1") (pinfunction "1_1") (pintype "passive"))
      (node (ref "C19") (pin "1") (pinfunction "1_1") (pintype "passive"))
      (node (ref "C20") (pin "1") (pinfunction "1_1") (pintype "passive"))
      (node (ref "C21") (pin "2") (pinfunction "2_2") (pintype "passive"))
      (node (ref "C22") (pin "2") (pinfunction "2_2") (pintype "passive"))
      (node (ref "C4") (pin "1") (pinfunction "1_1") (pintype "passive"))
      (node (ref "C5") (pin "1") (pinfunction "1_1") (pintype "passive"))
      (node (ref "R11") (pin "1") (pinfunction "1_1") (pintype "passive"))
      (node (ref "U1") (pin "109") (pinfunction "RDVDD_109") (pintype "passive"))
      (node (ref "U1") (pin "110") (pinfunction "RCVDD_110") (pintype "passive"))
      (node (ref "U1") (pin "118") (pinfunction "CVDD_118") (pintype "power_in"))
      (node (ref "U1") (pin "132") (pinfunction "CVDD_132") (pintype "power_in"))
      (node (ref "U1") (pin "18") (pinfunction "CVDD_18") (pintype "power_in"))
      (node (ref "U1") (pin "29") (pinfunction "CVDD_29") (pintype "power_in"))
      (node (ref "U1") (pin "30") (pinfunction "CVDD_30") (pintype "power_in"))
      (node (ref "U1") (pin "41") (pinfunction "CVDD_41") (pintype "power_in"))
      (node (ref "U1") (pin "53") (pinfunction "CVDD_53") (pintype "power_in"))
      (node (ref "U1") (pin "68") (pinfunction "CVDD_68") (pintype "power_in"))
      (node (ref "U1") (pin "78") (pinfunction "CVDD_78") (pintype "power_in"))
      (node (ref "U1") (pin "83") (pinfunction "CVDD_83") (pintype "power_in"))
      (node (ref "U1") (pin "87") (pinfunction "CVDD_87") (pintype "power_in"))
      (node (ref "U1") (pin "95") (pinfunction "CVDD_95") (pintype "passive"))
      (node (ref "U2") (pin "3") (pinfunction "SENSE3_3") (pintype "passive"))
      (node (ref "U5") (pin "4") (pintype "passive"))
    )
    (net (code "110") (name "VDD3.3") (class "Default")
      (node (ref "C10") (pin "1") (pinfunction "1_1") (pintype "passive"))
      (node (ref "C11") (pin "1") (pinfunction "1_1") (pintype "passive"))
      (node (ref "C12") (pin "1") (pinfunction "1_1") (pintype "passive"))
      (node (ref "C13") (pin "1") (pinfunction "1_1") (pintype "passive"))
      (node (ref "C2") (pin "1") (pinfunction "1_1") (pintype "passive"))
      (node (ref "C3") (pin "1") (pinfunction "1_1") (pintype "passive"))
      (node (ref "C6") (pin "1") (pinfunction "1_1") (pintype "passive"))
      (node (ref "C7") (pin "1") (pinfunction "1_1") (pintype "passive"))
      (node (ref "C8") (pin "1") (pinfunction "1_1") (pintype "passive"))
      (node (ref "C9") (pin "1") (pinfunction "1_1") (pintype "passive"))
      (node (ref "J2") (pin "5") (pinfunction "5_5") (pintype "passive"))
      (node (ref "J7") (pin "12") (pinfunction "12_12") (pintype "passive"))
      (node (ref "J8") (pin "11") (pinfunction "11_11") (pintype "passive"))
      (node (ref "J8") (pin "12") (pinfunction "12_12") (pintype "passive"))
      (node (ref "R17") (pin "1") (pinfunction "1_1") (pintype "passive"))
      (node (ref "R18") (pin "1") (pinfunction "1_1") (pintype "passive"))
      (node (ref "R2") (pin "1") (pinfunction "1_1") (pintype "passive"))
      (node (ref "R21") (pin "1") (pinfunction "1_1") (pintype "passive"))
      (node (ref "R22") (pin "2") (pinfunction "2_2") (pintype "passive"))
      (node (ref "R23") (pin "1") (pinfunction "1_1") (pintype "passive"))
      (node (ref "R3") (pin "2") (pinfunction "2_2") (pintype "passive"))
      (node (ref "R4") (pin "2") (pinfunction "2_2") (pintype "passive"))
      (node (ref "R5") (pin "2") (pinfunction "2_2") (pintype "passive"))
      (node (ref "R6") (pin "2") (pinfunction "2_2") (pintype "passive"))
      (node (ref "R7") (pin "2") (pinfunction "2_2") (pintype "passive"))
      (node (ref "R8") (pin "2") (pinfunction "2_2") (pintype "passive"))
      (node (ref "U1") (pin "104") (pinfunction "ADVDD_104") (pintype "power_in"))
      (node (ref "U1") (pin "107") (pinfunction "AVDD_107") (pintype "power_in"))
      (node (ref "U1") (pin "126") (pinfunction "DVDD_126") (pintype "power_in"))
      (node (ref "U1") (pin "139") (pinfunction "DVDD_139") (pintype "power_in"))
      (node (ref "U1") (pin "24") (pinfunction "DVDD_24") (pintype "power_in"))
      (node (ref "U1") (pin "49") (pinfunction "DVDD_49") (pintype "power_in"))
      (node (ref "U1") (pin "5") (pinfunction "USBVDD_5") (pintype "passive"))
      (node (ref "U1") (pin "56") (pinfunction "DVDD_56") (pintype "power_in"))
      (node (ref "U1") (pin "72") (pinfunction "DVDD_72") (pintype "power_in"))
      (node (ref "U1") (pin "8") (pinfunction "DVDD_8") (pintype "power_in"))
      (node (ref "U1") (pin "88") (pinfunction "DVDD_88") (pintype "power_in"))
      (node (ref "U1") (pin "98") (pinfunction "DVDD_98") (pintype "power_in"))
      (node (ref "U2") (pin "1") (pinfunction "SENSE1_1") (pintype "passive"))
      (node (ref "U2") (pin "8") (pinfunction "VDD_8") (pintype "passive"))
      (node (ref "U3") (pin "8") (pinfunction "VCC_8") (pintype "passive"))
      (node (ref "U4") (pin "4") (pintype "passive"))
      (node (ref "U5") (pin "3") (pinfunction "IN_3") (pintype "input"))
      (node (ref "V1") (pin "1") (pinfunction "1_1") (pintype "passive"))
      (node (ref "V2") (pin "1") (pinfunction "1_1") (pintype "passive"))
    )
    (net (code "111") (name "VDD5.0") (class "Default")
      (node (ref "F1") (pin "1") (pintype "input"))
      (node (ref "J1") (pin "1") (pinfunction "VBUS_1") (pintype "passive"))
      (node (ref "J7") (pin "15") (pinfunction "15_15") (pintype "passive"))
      (node (ref "J8") (pin "15") (pinfunction "15_15") (pintype "passive"))
    )
    (net (code "112") (name "unconnected-(J1-ID-Pad4)") (class "Default")
      (node (ref "J1") (pin "4") (pinfunction "ID_4") (pintype "passive"))
    )
    (net (code "113") (name "unconnected-(J2-Pad6)") (class "Default")
      (node (ref "J2") (pin "6") (pinfunction "6_6") (pintype "passive+no_connect"))
    )
    (net (code "114") (name "unconnected-(U1-CLKOUT-Pad15)") (class "Default")
      (node (ref "U1") (pin "15") (pinfunction "CLKOUT_15") (pintype "passive"))
    )
    (net (code "115") (name "unconnected-(U2-REST-Pad6)") (class "Default")
      (node (ref "U2") (pin "6") (pinfunction "REST_6") (pintype "passive"))
    )
    (net (code "116") (name "unconnected-(U4-OUT-Pad2)") (class "Default")
      (node (ref "U4") (pin "2") (pinfunction "OUT_2") (pintype "power_in"))
    )
    (net (code "117") (name "unconnected-(U5-OUT-Pad2)") (class "Default")
      (node (ref "U5") (pin "2") (pinfunction "OUT_2") (pintype "power_in"))
    )
  )
)
